# Arduino_MEGA_2560-Rev3_1.net
KiCad netlist of a schematic drawn in Altium Designer
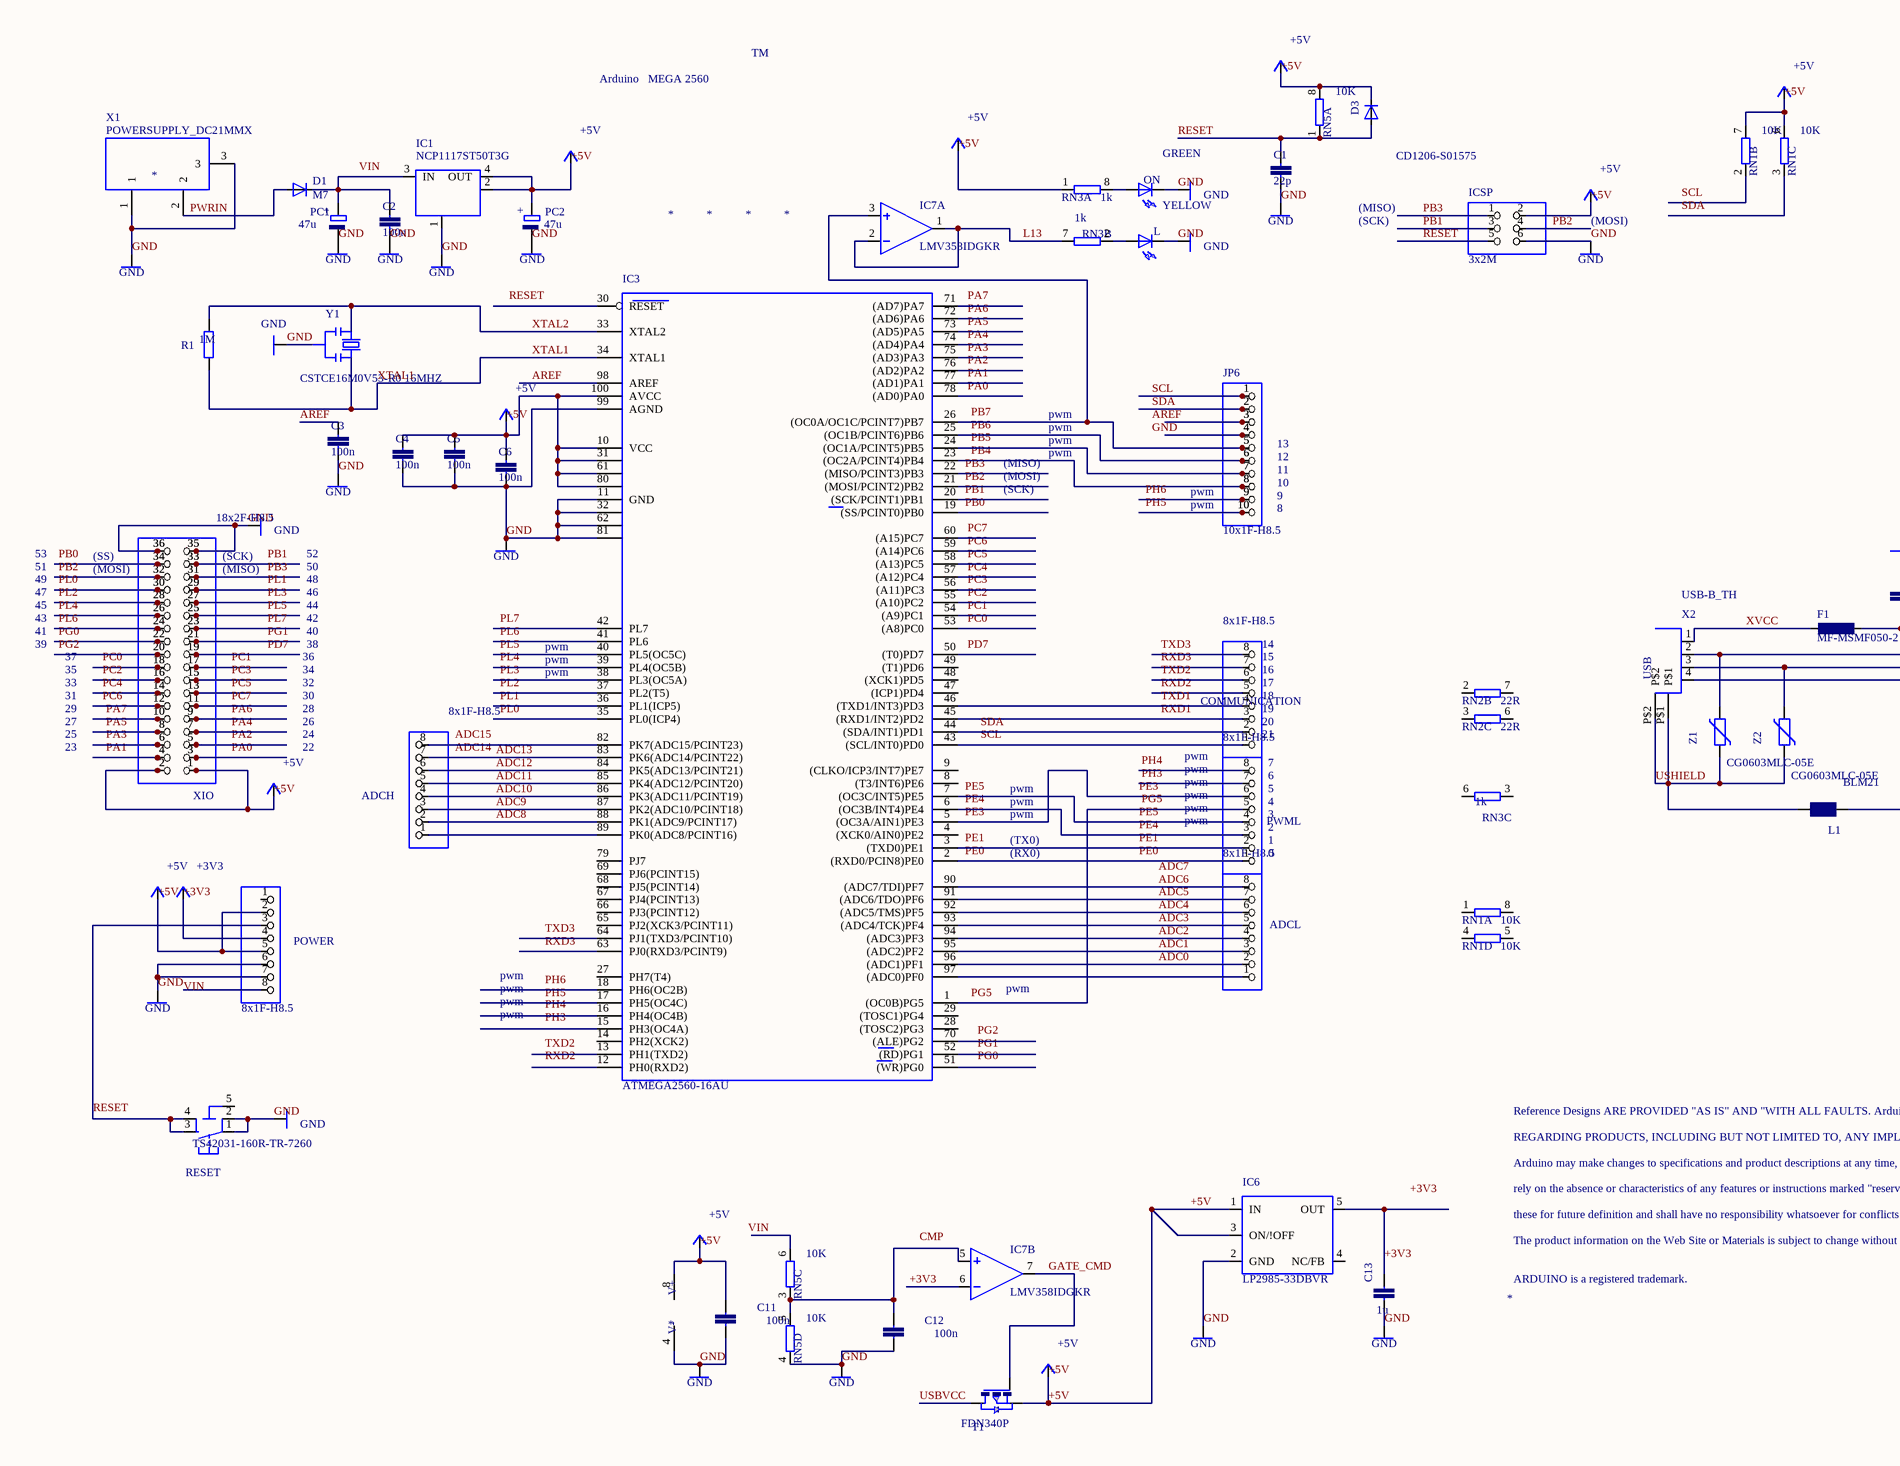
[diagram p0: Arduino_MEGA_2560-Rev3_1.SchDoc, left]
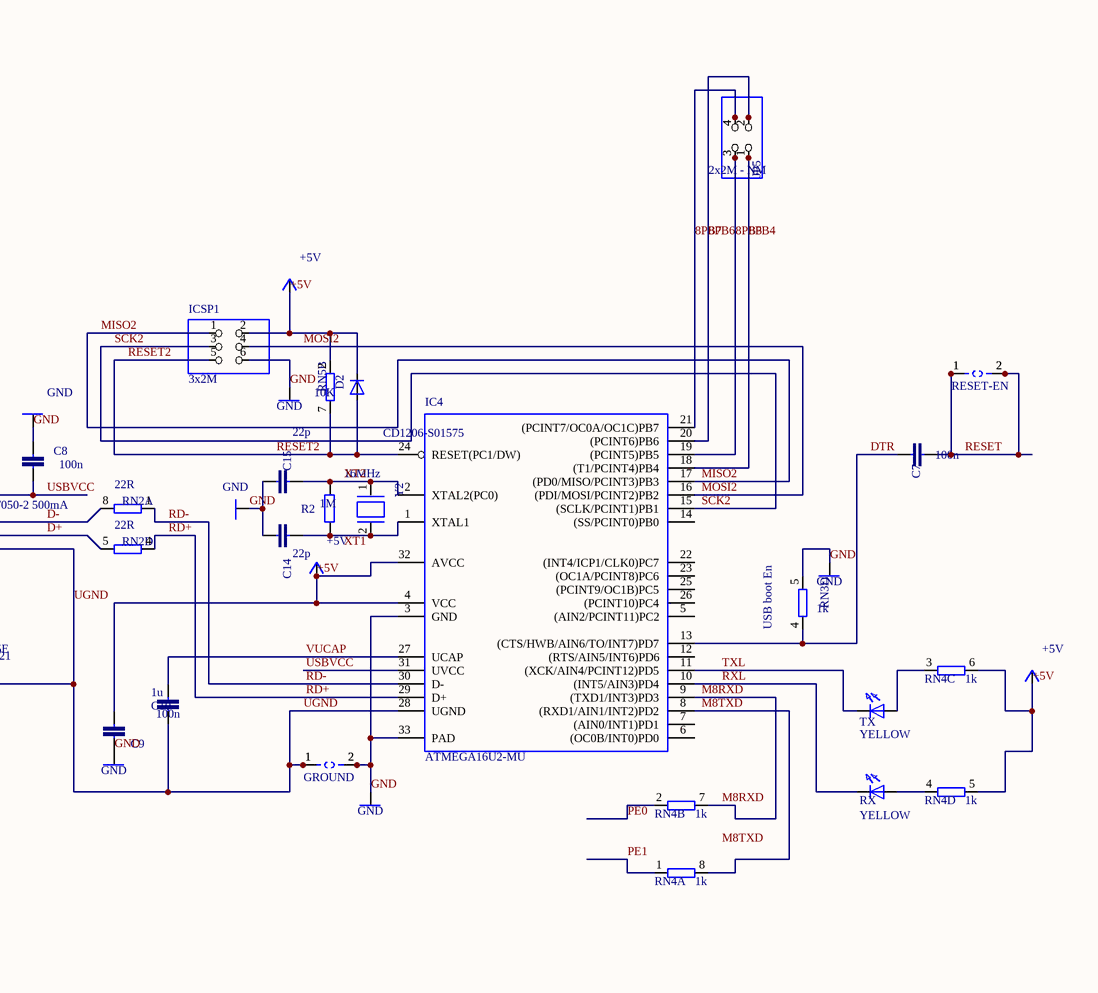
[diagram p1: Arduino_MEGA_2560-Rev3_1.SchDoc, right]

(export (version "E")
  (design (tool "Eeschema 10.0.6"))
  (components
    (comp (ref "+3V3") (value "+3V3") (libsource (lib "supply1") (part "+3V3")))
    (comp (ref "ADCH") (value "8x1F-H8.5") (footprint "1X08") (libsource (lib "SmartPrj") (part "PINHD-1X8")))
    (comp (ref "ADCL") (value "8x1F-H8.5") (footprint "1X08") (libsource (lib "SmartPrj") (part "PINHD-1X8")))
    (comp (ref "C1")
      (value "22p")
      (footprint "C0603-ROUND")
      (libsource (lib "SmartPrj") (part "C-EU0603-RND"))
    )
    (comp (ref "C2")
      (value "100n")
      (footprint "C0603-ROUND")
      (libsource (lib "SmartPrj") (part "C-EU0603-RND"))
    )
    (comp (ref "C3")
      (value "100n")
      (footprint "C0603-ROUND")
      (libsource (lib "SmartPrj") (part "C-EU0603-RND"))
    )
    (comp (ref "C4")
      (value "100n")
      (footprint "C0603-ROUND")
      (libsource (lib "SmartPrj") (part "C-EU0603-RND"))
    )
    (comp (ref "C5")
      (value "100n")
      (footprint "C0603-ROUND")
      (libsource (lib "SmartPrj") (part "C-EU0603-RND"))
    )
    (comp (ref "C6")
      (value "100n")
      (footprint "C0603-ROUND")
      (libsource (lib "SmartPrj") (part "C-EU0603-RND"))
    )
    (comp (ref "C7") (value "100n") (footprint "C0603-ROUND") (libsource (lib "") (part "C-EU0603-RND_4")))
    (comp (ref "C8") (value "100n") (footprint "C0603-ROUND") (libsource (lib "") (part "C-EU0603-RND_5")))
    (comp (ref "C9") (value "100n") (footprint "C0603-ROUND") (libsource (lib "") (part "C-EU0603-RND_3")))
    (comp (ref "C10")
      (value "1u")
      (footprint "C0603-ROUND")
      (libsource (lib "SmartPrj") (part "C-EU0603-RND"))
    )
    (comp (ref "C11") (value "100n") (footprint "C0603-ROUND") (libsource (lib "") (part "C-EU0603-RND_1")))
    (comp (ref "C12") (value "100n") (footprint "C0603-ROUND") (libsource (lib "") (part "C-EU0603-RND_1")))
    (comp (ref "C13") (value "1u") (footprint "C0603-ROUND") (libsource (lib "") (part "C-EU0603-RND_5")))
    (comp (ref "C14") (value "22p") (footprint "C0603-ROUND") (libsource (lib "") (part "C-EU0603-RND_2")))
    (comp (ref "C15") (value "22p") (footprint "C0603-ROUND") (libsource (lib "") (part "C-EU0603-RND_2")))
    (comp (ref "COMMUNICATION")
      (value "8x1F-H8.5")
      (footprint "1X08")
      (libsource (lib "SmartPrj") (part "PINHD-1X8"))
    )
    (comp (ref "D1") (value "M7") (footprint "SMB") (libsource (lib "diode") (part "DIODE-SMB")))
    (comp (ref "D2")
      (value "CD1206-S01575")
      (footprint "MINIMELF")
      (libsource (lib "diode") (part "DIODE-MINIMELF"))
    )
    (comp (ref "D3")
      (value "CD1206-S01575")
      (footprint "MINIMELF")
      (libsource (lib "diode") (part "DIODE-MINIMELF"))
    )
    (comp (ref "F1")
      (value "MF-MSMF050-2 500mA")
      (footprint "L1812")
      (libsource (lib "rcl") (part "L-EUL1812"))
    )
    (comp (ref "FD1")
      (value "*")
      (footprint "FIDUCIA-MOUNT")
      (libsource (lib "SmartPrj") (part "FIDUCIALMOUNT"))
    )
    (comp (ref "FD2")
      (value "*")
      (footprint "FIDUCIA-MOUNT")
      (libsource (lib "SmartPrj") (part "FIDUCIALMOUNT"))
    )
    (comp (ref "FD3")
      (value "*")
      (footprint "FIDUCIA-MOUNT")
      (libsource (lib "SmartPrj") (part "FIDUCIALMOUNT"))
    )
    (comp (ref "FD4")
      (value "*")
      (footprint "FIDUCIA-MOUNT")
      (libsource (lib "SmartPrj") (part "FIDUCIALMOUNT"))
    )
    (comp (ref "GND1") (value "GND") (libsource (lib "") (part "GND_1")))
    (comp (ref "GND2") (value "GND") (libsource (lib "") (part "GND_1")))
    (comp (ref "GND3") (value "GND") (libsource (lib "supply1") (part "GND")))
    (comp (ref "GND4") (value "GND") (libsource (lib "") (part "GND_1")))
    (comp (ref "GND5") (value "GND") (libsource (lib "") (part "GND_1")))
    (comp (ref "GND7") (value "GND") (libsource (lib "") (part "GND_1")))
    (comp (ref "GND8") (value "GND") (libsource (lib "") (part "GND_1")))
    (comp (ref "GND9") (value "GND") (libsource (lib "") (part "GND_1")))
    (comp (ref "GND10") (value "GND") (libsource (lib "") (part "GND_1")))
    (comp (ref "GND11") (value "GND") (libsource (lib "") (part "GND_1")))
    (comp (ref "GND12") (value "GND") (libsource (lib "supply1") (part "GND")))
    (comp (ref "GND13") (value "GND") (libsource (lib "") (part "GND_1")))
    (comp (ref "GND14") (value "GND") (libsource (lib "") (part "GND_1")))
    (comp (ref "GND15") (value "GND") (libsource (lib "") (part "GND_1")))
    (comp (ref "GND16") (value "GND") (libsource (lib "") (part "GND_1")))
    (comp (ref "GND18") (value "GND") (libsource (lib "") (part "GND_1")))
    (comp (ref "GND19") (value "GND") (libsource (lib "") (part "GND_1")))
    (comp (ref "GND20") (value "GND") (libsource (lib "supply1") (part "GND")))
    (comp (ref "GND22") (value "GND") (libsource (lib "") (part "GND_1")))
    (comp (ref "GND23") (value "GND") (libsource (lib "") (part "GND_1")))
    (comp (ref "GND24") (value "GND") (libsource (lib "") (part "GND_1")))
    (comp (ref "GND25") (value "GND") (libsource (lib "supply1") (part "GND")))
    (comp (ref "GND26") (value "GND") (libsource (lib "") (part "GND_1")))
    (comp (ref "GND28") (value "GND") (libsource (lib "") (part "GND_1")))
    (comp (ref "GND30") (value "GND") (libsource (lib "") (part "GND_1")))
    (comp (ref "GROUND") (value "~") (footprint "SJ") (libsource (lib "jumper") (part "SJ")))
    (comp (ref "IC1")
      (value "NCP1117ST50T3G")
      (footprint "SOT223")
      (libsource (lib "linear") (part "MC33269ST-3.3T3"))
    )
    (comp (ref "IC3")
      (value "ATMEGA2560-16AU")
      (footprint "TQFP100")
      (libsource (lib "SmartPrj") (part "ATMEGA25602560-16AU"))
    )
    (comp (ref "IC4")
      (value "ATMEGA16U2-MU")
      (footprint "MLF32")
      (libsource (lib "SmartPrj") (part "ATMEGA16U2-MU"))
    )
    (comp (ref "IC6")
      (value "LP2985-33DBVR")
      (footprint "SOT23-DBV")
      (libsource (lib "SmartPrj") (part "LP2985-XXDBVR33"))
    )
    (comp (ref "IC7")
      (value "LMV358IDGKR")
      (footprint "MSOP08")
      (libsource (lib "linear") (part "LMV358MMX"))
    )
    (comp (ref "ICSP") (value "3x2M") (footprint "2X03") (libsource (lib "SmartPrj") (part "PINHD-2X3")))
    (comp (ref "ICSP1") (value "3x2M") (footprint "2X03") (libsource (lib "SmartPrj") (part "PINHD-2X3")))
    (comp (ref "JP5") (value "2x2M - NM") (footprint "2X02") (libsource (lib "SmartPrj") (part "PINHD-2X2")))
    (comp (ref "JP6")
      (value "10x1F-H8.5")
      (footprint "1X10")
      (libsource (lib "SmartPrj") (part "PINHD-1X10_ARD"))
    )
    (comp (ref "L")
      (value "YELLOW")
      (footprint "CHIP-LED0805")
      (libsource (lib "led") (part "LEDCHIP-LED0805"))
    )
    (comp (ref "L1")
      (value "BLM21")
      (footprint "0805")
      (libsource (lib "wuerth-elektronik") (part "WE-CBF_0805"))
    )
    (comp (ref "ON")
      (value "GREEN")
      (footprint "CHIP-LED0805")
      (libsource (lib "led") (part "LEDCHIP-LED0805"))
    )
    (comp (ref "P+1") (value "+5V") (libsource (lib "supply1") (part "+5V")))
    (comp (ref "P+2") (value "+5V") (libsource (lib "") (part "+5V_1")))
    (comp (ref "P+3") (value "+5V") (libsource (lib "supply1") (part "+5V")))
    (comp (ref "P+4") (value "+5V") (libsource (lib "supply1") (part "+5V")))
    (comp (ref "P+5") (value "+5V") (libsource (lib "supply1") (part "+5V")))
    (comp (ref "P+7") (value "+5V") (libsource (lib "supply1") (part "+5V")))
    (comp (ref "P+8") (value "+5V") (libsource (lib "supply1") (part "+5V")))
    (comp (ref "P+9") (value "+5V") (libsource (lib "supply1") (part "+5V")))
    (comp (ref "P+10") (value "+5V") (libsource (lib "supply1") (part "+5V")))
    (comp (ref "P+11") (value "+5V") (libsource (lib "") (part "+5V_1")))
    (comp (ref "P+12") (value "+5V") (libsource (lib "supply1") (part "+5V")))
    (comp (ref "P+13") (value "+5V") (libsource (lib "supply1") (part "+5V")))
    (comp (ref "P+14") (value "+5V") (libsource (lib "supply1") (part "+5V")))
    (comp (ref "PC1") (value "47u") (footprint "PANASONIC_D") (libsource (lib "rcl") (part "CPOL-EUD")))
    (comp (ref "PC2") (value "47u") (footprint "PANASONIC_D") (libsource (lib "rcl") (part "CPOL-EUD")))
    (comp (ref "POWER")
      (value "8x1F-H8.5")
      (footprint "1X08")
      (libsource (lib "SmartPrj") (part "PINHD-1X8"))
    )
    (comp (ref "PWML") (value "8x1F-H8.5") (footprint "1X08") (libsource (lib "SmartPrj") (part "PINHD-1X8")))
    (comp (ref "R1") (value "1M") (footprint "R0603-ROUND") (libsource (lib "SmartPrj") (part "R-EU_R0603")))
    (comp (ref "R2") (value "1M") (footprint "R0603-ROUND") (libsource (lib "SmartPrj") (part "R-EU_R0603")))
    (comp (ref "RESET")
      (value "TS42031-160R-TR-7260")
      (footprint "TS42")
      (libsource (lib "SmartPrj") (part "TS42"))
    )
    (comp (ref "RESET-EN") (value "~") (footprint "SJ") (libsource (lib "jumper") (part "SJ")))
    (comp (ref "RN1") (value "10K") (footprint "CAT16") (libsource (lib "") (part "4R-NCAT16_7")))
    (comp (ref "RN2") (value "22R") (footprint "CAY16") (libsource (lib "") (part "4R-NCAY16_4")))
    (comp (ref "RN3") (value "1k") (footprint "CAY16") (libsource (lib "") (part "4R-NCAY16_6")))
    (comp (ref "RN4") (value "1k") (footprint "CAY16") (libsource (lib "") (part "4R-NCAY16_1")))
    (comp (ref "RN5") (value "10K") (footprint "CAT16") (libsource (lib "") (part "4R-NCAT16_3")))
    (comp (ref "RX")
      (value "YELLOW")
      (footprint "CHIP-LED0805")
      (libsource (lib "") (part "LEDCHIP-LED0805_1"))
    )
    (comp (ref "T1") (value "FDN340P") (footprint "SOT-23") (libsource (lib "zetex") (part "PMOSSOT23")))
    (comp (ref "TX")
      (value "YELLOW")
      (footprint "CHIP-LED0805")
      (libsource (lib "") (part "LEDCHIP-LED0805_1"))
    )
    (comp (ref "U$1") (value "*") (footprint "DISCLAIMER") (libsource (lib "SmartPrj") (part "DISCLAIMER")))
    (comp (ref "X1")
      (value "*")
      (footprint "POWERSUPPLY_DC-21MM")
      (libsource (lib "SmartPrj") (part "POWERSUPPLY_DC21MMX"))
    )
    (comp (ref "X2") (value "USB-B_TH") (footprint "PN61729") (libsource (lib "SmartPrj") (part "PN61729")))
    (comp (ref "XIO")
      (value "18x2F-H8.5")
      (footprint "2X18")
      (libsource (lib "SmartPrj") (part "PINHD-2X18"))
    )
    (comp (ref "Y1")
      (value "CSTCE16M0V53-R0 16MHZ")
      (footprint "RESONATOR")
      (libsource (lib "SmartPrj") (part "RESONATORMU"))
    )
    (comp (ref "Y2") (value "16MHz") (footprint "QS") (libsource (lib "SmartPrj") (part "XTAL/S")))
    (comp (ref "Z1")
      (value "CG0603MLC-05E")
      (footprint "CT/CN0603")
      (libsource (lib "varistor") (part "VARISTORCN0603"))
    )
    (comp (ref "Z2")
      (value "CG0603MLC-05E")
      (footprint "CT/CN0603")
      (libsource (lib "varistor") (part "VARISTORCN0603"))
    )
  )
  (nets
    (net (code "1") (name "/+3V3") (class "Default")
      (node (ref "+3V3") (pin "0") (pinfunction "+3V3_0") (pintype "passive"))
      (node (ref "C13") (pin "2") (pinfunction "2_2") (pintype "passive"))
      (node (ref "IC6") (pin "5") (pinfunction "OUT_5") (pintype "passive"))
      (node (ref "IC7") (pin "6") (pinfunction "-IN_6") (pintype "passive"))
      (node (ref "POWER") (pin "4") (pinfunction "4_4") (pintype "passive"))
    )
    (net (code "2") (name "/+5V") (class "Default")
      (node (ref "C11") (pin "2") (pinfunction "2_2") (pintype "passive"))
      (node (ref "C4") (pin "1") (pinfunction "1_1") (pintype "passive"))
      (node (ref "C5") (pin "1") (pinfunction "1_1") (pintype "passive"))
      (node (ref "C6") (pin "1") (pinfunction "1_1") (pintype "passive"))
      (node (ref "C9") (pin "1") (pinfunction "1_1") (pintype "passive"))
      (node (ref "D2") (pin "C") (pinfunction "C_C") (pintype "passive"))
      (node (ref "D3") (pin "C") (pinfunction "C_C") (pintype "passive"))
      (node (ref "IC1") (pin "2") (pinfunction "OUT@1_2") (pintype "passive"))
      (node (ref "IC1") (pin "4") (pinfunction "OUT_4") (pintype "passive"))
      (node (ref "IC3") (pin "10") (pinfunction "VCC_10") (pintype "passive"))
      (node (ref "IC3") (pin "100") (pinfunction "AVCC_100") (pintype "passive"))
      (node (ref "IC3") (pin "31") (pinfunction "VCC1_31") (pintype "passive"))
      (node (ref "IC3") (pin "61") (pinfunction "VCC2_61") (pintype "passive"))
      (node (ref "IC3") (pin "80") (pinfunction "VCC3_80") (pintype "passive"))
      (node (ref "IC4") (pin "32") (pinfunction "AVCC_32") (pintype "passive"))
      (node (ref "IC4") (pin "4") (pinfunction "VCC_4") (pintype "passive"))
      (node (ref "IC6") (pin "1") (pinfunction "IN_1") (pintype "passive"))
      (node (ref "IC6") (pin "3") (pinfunction "ON/!OFF_3") (pintype "passive"))
      (node (ref "IC7") (pin "8") (pinfunction "V+_8") (pintype "passive"))
      (node (ref "ICSP") (pin "2") (pinfunction "2_2") (pintype "passive"))
      (node (ref "ICSP1") (pin "2") (pinfunction "2_2") (pintype "passive"))
      (node (ref "P+1") (pin "0") (pinfunction "+5V_0") (pintype "passive"))
      (node (ref "P+10") (pin "0") (pinfunction "+5V_0") (pintype "passive"))
      (node (ref "P+11") (pin "0") (pinfunction "+5V_0") (pintype "passive"))
      (node (ref "P+12") (pin "0") (pinfunction "+5V_0") (pintype "passive"))
      (node (ref "P+13") (pin "0") (pinfunction "+5V_0") (pintype "passive"))
      (node (ref "P+14") (pin "0") (pinfunction "+5V_0") (pintype "passive"))
      (node (ref "P+2") (pin "0") (pinfunction "+5V_0") (pintype "passive"))
      (node (ref "P+3") (pin "0") (pinfunction "+5V_0") (pintype "passive"))
      (node (ref "P+4") (pin "0") (pinfunction "+5V_0") (pintype "passive"))
      (node (ref "P+5") (pin "0") (pinfunction "+5V_0") (pintype "passive"))
      (node (ref "P+7") (pin "0") (pinfunction "+5V_0") (pintype "passive"))
      (node (ref "P+8") (pin "0") (pinfunction "+5V_0") (pintype "passive"))
      (node (ref "P+9") (pin "0") (pinfunction "+5V_0") (pintype "passive"))
      (node (ref "PC2") (pin "+") (pinfunction "+_+") (pintype "passive"))
      (node (ref "POWER") (pin "2") (pinfunction "2_2") (pintype "passive"))
      (node (ref "POWER") (pin "5") (pinfunction "5_5") (pintype "passive"))
      (node (ref "RN1") (pin "6") (pinfunction "2_6") (pintype "passive"))
      (node (ref "RN1") (pin "7") (pinfunction "2_7") (pintype "passive"))
      (node (ref "RN3") (pin "1") (pinfunction "1_1") (pintype "passive"))
      (node (ref "RN4") (pin "5") (pinfunction "2_5") (pintype "passive"))
      (node (ref "RN4") (pin "6") (pinfunction "2_6") (pintype "passive"))
      (node (ref "RN5") (pin "2") (pinfunction "1_2") (pintype "passive"))
      (node (ref "RN5") (pin "8") (pinfunction "2_8") (pintype "passive"))
      (node (ref "T1") (pin "2") (pinfunction "S_2") (pintype "passive"))
      (node (ref "XIO") (pin "1") (pinfunction "1_1") (pintype "passive"))
      (node (ref "XIO") (pin "2") (pinfunction "2_2") (pintype "passive"))
    )
    (net (code "3") (name "/8PB4") (class "Default")
      (node (ref "IC4") (pin "18") (pinfunction "(T1/PCINT4)PB4_18") (pintype "passive"))
      (node (ref "JP5") (pin "1") (pinfunction "1_1") (pintype "passive"))
    )
    (net (code "4") (name "/8PB5") (class "Default")
      (node (ref "IC4") (pin "19") (pinfunction "(PCINT5)PB5_19") (pintype "passive"))
      (node (ref "JP5") (pin "3") (pinfunction "3_3") (pintype "passive"))
    )
    (net (code "5") (name "/8PB6") (class "Default")
      (node (ref "IC4") (pin "20") (pinfunction "(PCINT6)PB6_20") (pintype "passive"))
      (node (ref "JP5") (pin "2") (pinfunction "2_2") (pintype "passive"))
    )
    (net (code "6") (name "/8PB7") (class "Default")
      (node (ref "IC4") (pin "21") (pinfunction "(PCINT7/OC0A/OC1C)PB7_21") (pintype "passive"))
      (node (ref "JP5") (pin "4") (pinfunction "4_4") (pintype "passive"))
    )
    (net (code "7") (name "/ADC0") (class "Default")
      (node (ref "ADCL") (pin "2") (pinfunction "2_2") (pintype "passive"))
      (node (ref "IC3") (pin "96") (pinfunction "(ADC1)PF1_96") (pintype "passive"))
    )
    (net (code "8") (name "/ADC1") (class "Default")
      (node (ref "ADCL") (pin "3") (pinfunction "3_3") (pintype "passive"))
      (node (ref "IC3") (pin "95") (pinfunction "(ADC2)PF2_95") (pintype "passive"))
    )
    (net (code "9") (name "/ADC2") (class "Default")
      (node (ref "ADCL") (pin "4") (pinfunction "4_4") (pintype "passive"))
      (node (ref "IC3") (pin "94") (pinfunction "(ADC3)PF3_94") (pintype "passive"))
    )
    (net (code "10") (name "/ADC3") (class "Default")
      (node (ref "ADCL") (pin "5") (pinfunction "5_5") (pintype "passive"))
      (node (ref "IC3") (pin "93") (pinfunction "(ADC4/TCK)PF4_93") (pintype "passive"))
    )
    (net (code "11") (name "/ADC4") (class "Default")
      (node (ref "ADCL") (pin "6") (pinfunction "6_6") (pintype "passive"))
      (node (ref "IC3") (pin "92") (pinfunction "(ADC5/TMS)PF5_92") (pintype "passive"))
    )
    (net (code "12") (name "/ADC5") (class "Default")
      (node (ref "ADCL") (pin "7") (pinfunction "7_7") (pintype "passive"))
      (node (ref "IC3") (pin "91") (pinfunction "(ADC6/TDO)PF6_91") (pintype "passive"))
    )
    (net (code "13") (name "/ADC6") (class "Default")
      (node (ref "ADCL") (pin "8") (pinfunction "8_8") (pintype "passive"))
      (node (ref "IC3") (pin "90") (pinfunction "(ADC7/TDI)PF7_90") (pintype "passive"))
    )
    (net (code "15") (name "/ADC8") (class "Default")
      (node (ref "ADCH") (pin "2") (pinfunction "2_2") (pintype "passive"))
      (node (ref "IC3") (pin "88") (pinfunction "PK1(ADC9/PCINT17)_88") (pintype "passive"))
    )
    (net (code "16") (name "/ADC9") (class "Default")
      (node (ref "ADCH") (pin "3") (pinfunction "3_3") (pintype "passive"))
      (node (ref "IC3") (pin "87") (pinfunction "PK2(ADC10/PCINT18)_87") (pintype "passive"))
    )
    (net (code "17") (name "/ADC10") (class "Default")
      (node (ref "ADCH") (pin "4") (pinfunction "4_4") (pintype "passive"))
      (node (ref "IC3") (pin "86") (pinfunction "PK3(ADC11/PCINT19)_86") (pintype "passive"))
    )
    (net (code "18") (name "/ADC11") (class "Default")
      (node (ref "ADCH") (pin "5") (pinfunction "5_5") (pintype "passive"))
      (node (ref "IC3") (pin "85") (pinfunction "PK4(ADC12/PCINT20)_85") (pintype "passive"))
    )
    (net (code "19") (name "/ADC12") (class "Default")
      (node (ref "ADCH") (pin "6") (pinfunction "6_6") (pintype "passive"))
      (node (ref "IC3") (pin "84") (pinfunction "PK5(ADC13/PCINT21)_84") (pintype "passive"))
    )
    (net (code "20") (name "/ADC13") (class "Default")
      (node (ref "ADCH") (pin "7") (pinfunction "7_7") (pintype "passive"))
      (node (ref "IC3") (pin "83") (pinfunction "PK6(ADC14/PCINT22)_83") (pintype "passive"))
    )
    (net (code "23") (name "/AREF") (class "Default")
      (node (ref "C3") (pin "1") (pinfunction "1_1") (pintype "passive"))
      (node (ref "IC3") (pin "98") (pinfunction "AREF_98") (pintype "passive"))
    )
    (net (code "25") (name "/D+") (class "Default")
      (node (ref "RN2") (pin "5") (pinfunction "2_5") (pintype "passive"))
      (node (ref "X2") (pin "3") (pinfunction "3_3") (pintype "passive"))
      (node (ref "Z2") (pin "2") (pinfunction "2_2") (pintype "passive"))
    )
    (net (code "26") (name "/D-") (class "Default")
      (node (ref "RN2") (pin "8") (pinfunction "2_8") (pintype "passive"))
      (node (ref "X2") (pin "2") (pinfunction "2_2") (pintype "passive"))
      (node (ref "Z1") (pin "2") (pinfunction "2_2") (pintype "passive"))
    )
    (net (code "27") (name "/DTR") (class "Default")
      (node (ref "C7") (pin "1") (pinfunction "1_1") (pintype "passive"))
      (node (ref "IC4") (pin "13") (pinfunction "(CTS/HWB/AIN6/TO/INT7)PD7_13") (pintype "passive"))
      (node (ref "RN3") (pin "4") (pinfunction "1_4") (pintype "passive"))
    )
    (net (code "28") (name "/GATE_CMD") (class "Default")
      (node (ref "IC7") (pin "7") (pinfunction "OUT_7") (pintype "passive"))
      (node (ref "T1") (pin "3") (pinfunction "G_3") (pintype "passive"))
    )
    (net (code "29") (name "/GND") (class "Default")
      (node (ref "C1") (pin "2") (pinfunction "2_2") (pintype "passive"))
      (node (ref "C11") (pin "1") (pinfunction "1_1") (pintype "passive"))
      (node (ref "C12") (pin "1") (pinfunction "1_1") (pintype "passive"))
      (node (ref "C13") (pin "1") (pinfunction "1_1") (pintype "passive"))
      (node (ref "C14") (pin "2") (pinfunction "2_2") (pintype "passive"))
      (node (ref "C15") (pin "2") (pinfunction "2_2") (pintype "passive"))
      (node (ref "C2") (pin "2") (pinfunction "2_2") (pintype "passive"))
      (node (ref "C3") (pin "2") (pinfunction "2_2") (pintype "passive"))
      (node (ref "C4") (pin "2") (pinfunction "2_2") (pintype "passive"))
      (node (ref "C5") (pin "2") (pinfunction "2_2") (pintype "passive"))
      (node (ref "C6") (pin "2") (pinfunction "2_2") (pintype "passive"))
      (node (ref "C8") (pin "2") (pinfunction "2_2") (pintype "passive"))
      (node (ref "C9") (pin "2") (pinfunction "2_2") (pintype "passive"))
      (node (ref "GND1") (pin "0") (pinfunction "GND_0") (pintype "passive"))
      (node (ref "GND10") (pin "0") (pinfunction "GND_0") (pintype "passive"))
      (node (ref "GND11") (pin "0") (pinfunction "GND_0") (pintype "passive"))
      (node (ref "GND12") (pin "0") (pinfunction "GND_0") (pintype "passive"))
      (node (ref "GND13") (pin "0") (pinfunction "GND_0") (pintype "passive"))
      (node (ref "GND14") (pin "0") (pinfunction "GND_0") (pintype "passive"))
      (node (ref "GND15") (pin "0") (pinfunction "GND_0") (pintype "passive"))
      (node (ref "GND16") (pin "0") (pinfunction "GND_0") (pintype "passive"))
      (node (ref "GND18") (pin "0") (pinfunction "GND_0") (pintype "passive"))
      (node (ref "GND19") (pin "0") (pinfunction "GND_0") (pintype "passive"))
      (node (ref "GND2") (pin "0") (pinfunction "GND_0") (pintype "passive"))
      (node (ref "GND20") (pin "0") (pinfunction "GND_0") (pintype "passive"))
      (node (ref "GND22") (pin "0") (pinfunction "GND_0") (pintype "passive"))
      (node (ref "GND23") (pin "0") (pinfunction "GND_0") (pintype "passive"))
      (node (ref "GND24") (pin "0") (pinfunction "GND_0") (pintype "passive"))
      (node (ref "GND25") (pin "0") (pinfunction "GND_0") (pintype "passive"))
      (node (ref "GND26") (pin "0") (pinfunction "GND_0") (pintype "passive"))
      (node (ref "GND28") (pin "0") (pinfunction "GND_0") (pintype "passive"))
      (node (ref "GND3") (pin "0") (pinfunction "GND_0") (pintype "passive"))
      (node (ref "GND30") (pin "0") (pinfunction "GND_0") (pintype "passive"))
      (node (ref "GND4") (pin "0") (pinfunction "GND_0") (pintype "passive"))
      (node (ref "GND5") (pin "0") (pinfunction "GND_0") (pintype "passive"))
      (node (ref "GND7") (pin "0") (pinfunction "GND_0") (pintype "passive"))
      (node (ref "GND8") (pin "0") (pinfunction "GND_0") (pintype "passive"))
      (node (ref "GND9") (pin "0") (pinfunction "GND_0") (pintype "passive"))
      (node (ref "GROUND") (pin "2") (pinfunction "2_2") (pintype "passive"))
      (node (ref "IC1") (pin "1") (pinfunction "GND/ADJ_1") (pintype "passive"))
      (node (ref "IC3") (pin "11") (pinfunction "GND_11") (pintype "passive"))
      (node (ref "IC3") (pin "32") (pinfunction "GND1_32") (pintype "passive"))
      (node (ref "IC3") (pin "62") (pinfunction "GND2_62") (pintype "passive"))
      (node (ref "IC3") (pin "81") (pinfunction "GND3_81") (pintype "passive"))
      (node (ref "IC3") (pin "99") (pinfunction "AGND_99") (pintype "passive"))
      (node (ref "IC4") (pin "3") (pinfunction "GND_3") (pintype "passive"))
      (node (ref "IC4") (pin "33") (pinfunction "PAD_33") (pintype "passive"))
      (node (ref "IC6") (pin "2") (pinfunction "GND_2") (pintype "passive"))
      (node (ref "IC7") (pin "4") (pinfunction "V-_4") (pintype "passive"))
      (node (ref "ICSP") (pin "6") (pinfunction "6_6") (pintype "passive"))
      (node (ref "ICSP1") (pin "6") (pinfunction "6_6") (pintype "passive"))
      (node (ref "L") (pin "C") (pinfunction "C_C") (pintype "passive"))
      (node (ref "ON") (pin "C") (pinfunction "C_C") (pintype "passive"))
      (node (ref "PC1") (pin "-") (pinfunction "-_-") (pintype "passive"))
      (node (ref "PC2") (pin "-") (pinfunction "-_-") (pintype "passive"))
      (node (ref "POWER") (pin "6") (pinfunction "6_6") (pintype "passive"))
      (node (ref "POWER") (pin "7") (pinfunction "7_7") (pintype "passive"))
      (node (ref "RESET") (pin "1") (pinfunction "1_1") (pintype "passive"))
      (node (ref "RESET") (pin "2") (pinfunction "2_2") (pintype "passive"))
      (node (ref "RN3") (pin "5") (pinfunction "2_5") (pintype "passive"))
      (node (ref "RN5") (pin "4") (pinfunction "1_4") (pintype "passive"))
      (node (ref "X1") (pin "1") (pinfunction "1_1") (pintype "passive"))
      (node (ref "X1") (pin "3") (pinfunction "3_3") (pintype "passive"))
      (node (ref "XIO") (pin "35") (pinfunction "35_35") (pintype "passive"))
      (node (ref "XIO") (pin "36") (pinfunction "36_36") (pintype "passive"))
      (node (ref "Y1") (pin "2") (pinfunction "2_2") (pintype "passive"))
    )
    (net (code "30") (name "/L13") (class "Default")
      (node (ref "IC7") (pin "1") (pinfunction "OUT_1") (pintype "passive"))
      (node (ref "IC7") (pin "2") (pinfunction "-IN_2") (pintype "passive"))
      (node (ref "RN3") (pin "7") (pinfunction "2_7") (pintype "passive"))
    )
    (net (code "31") (name "/M8RXD") (class "Default")
      (node (ref "IC4") (pin "9") (pinfunction "(TXD1/INT3)PD3_9") (pintype "passive"))
      (node (ref "RN4") (pin "7") (pinfunction "2_7") (pintype "passive"))
    )
    (net (code "32") (name "/M8TXD") (class "Default")
      (node (ref "IC4") (pin "8") (pinfunction "(RXD1/AIN1/INT2)PD2_8") (pintype "passive"))
      (node (ref "RN4") (pin "8") (pinfunction "2_8") (pintype "passive"))
    )
    (net (code "33") (name "/MISO2") (class "Default")
      (node (ref "IC4") (pin "17") (pinfunction "(PD0/MISO/PCINT3)PB3_17") (pintype "passive"))
      (node (ref "ICSP1") (pin "1") (pinfunction "1_1") (pintype "passive"))
    )
    (net (code "34") (name "/MOSI2") (class "Default")
      (node (ref "IC4") (pin "16") (pinfunction "(PDI/MOSI/PCINT2)PB2_16") (pintype "passive"))
      (node (ref "ICSP1") (pin "4") (pinfunction "4_4") (pintype "passive"))
    )
    (net (code "44") (name "/PB1") (class "Default")
      (node (ref "ICSP") (pin "3") (pinfunction "3_3") (pintype "passive"))
    )
    (net (code "45") (name "/PB2") (class "Default")
      (node (ref "ICSP") (pin "4") (pinfunction "4_4") (pintype "passive"))
    )
    (net (code "46") (name "/PB3") (class "Default")
      (node (ref "ICSP") (pin "1") (pinfunction "1_1") (pintype "passive"))
    )
    (net (code "60") (name "/PE0") (class "Default")
      (node (ref "RN4") (pin "2") (pinfunction "1_2") (pintype "passive"))
    )
    (net (code "61") (name "/PE1") (class "Default")
      (node (ref "RN4") (pin "1") (pinfunction "1_1") (pintype "passive"))
    )
    (net (code "81") (name "/PWRIN") (class "Default")
      (node (ref "D1") (pin "A") (pinfunction "A_A") (pintype "passive"))
      (node (ref "X1") (pin "2") (pinfunction "2_2") (pintype "passive"))
    )
    (net (code "82") (name "/RD+") (class "Default")
      (node (ref "IC4") (pin "29") (pinfunction "D+_29") (pintype "passive"))
      (node (ref "RN2") (pin "4") (pinfunction "1_4") (pintype "passive"))
    )
    (net (code "83") (name "/RD-") (class "Default")
      (node (ref "IC4") (pin "30") (pinfunction "D-_30") (pintype "passive"))
      (node (ref "RN2") (pin "1") (pinfunction "1_1") (pintype "passive"))
    )
    (net (code "84") (name "/RESET") (class "Default")
      (node (ref "C1") (pin "1") (pinfunction "1_1") (pintype "passive"))
      (node (ref "C7") (pin "2") (pinfunction "2_2") (pintype "passive"))
      (node (ref "D3") (pin "A") (pinfunction "A_A") (pintype "passive"))
      (node (ref "ICSP") (pin "5") (pinfunction "5_5") (pintype "passive"))
      (node (ref "POWER") (pin "3") (pinfunction "3_3") (pintype "passive"))
      (node (ref "RESET") (pin "3") (pinfunction "3_3") (pintype "passive"))
      (node (ref "RESET") (pin "4") (pinfunction "4_4") (pintype "passive"))
      (node (ref "RESET-EN") (pin "1") (pinfunction "1_1") (pintype "passive"))
      (node (ref "RESET-EN") (pin "2") (pinfunction "2_2") (pintype "passive"))
      (node (ref "RN5") (pin "1") (pinfunction "1_1") (pintype "passive"))
    )
    (net (code "85") (name "/RESET2") (class "Default")
      (node (ref "D2") (pin "A") (pinfunction "A_A") (pintype "passive"))
      (node (ref "IC4") (pin "24") (pinfunction "RESET(PC1/DW)_24") (pintype "passive"))
      (node (ref "ICSP1") (pin "5") (pinfunction "5_5") (pintype "passive"))
      (node (ref "RN5") (pin "7") (pinfunction "2_7") (pintype "passive"))
    )
    (net (code "89") (name "/RXL") (class "Default")
      (node (ref "IC4") (pin "10") (pinfunction "(INT5/AIN3)PD4_10") (pintype "passive"))
      (node (ref "RX") (pin "C") (pinfunction "C_C") (pintype "passive"))
    )
    (net (code "90") (name "/SCK2") (class "Default")
      (node (ref "IC4") (pin "15") (pinfunction "(SCLK/PCINT1)PB1_15") (pintype "passive"))
      (node (ref "ICSP1") (pin "3") (pinfunction "3_3") (pintype "passive"))
    )
    (net (code "91") (name "/SCL") (class "Default")
      (node (ref "JP6") (pin "1") (pinfunction "1_1") (pintype "passive"))
    )
    (net (code "92") (name "/SDA") (class "Default")
      (node (ref "JP6") (pin "2") (pinfunction "2_2") (pintype "passive"))
    )
    (net (code "96") (name "/TXL") (class "Default")
      (node (ref "IC4") (pin "11") (pinfunction "(XCK/AIN4/PCINT12)PD5_11") (pintype "passive"))
      (node (ref "TX") (pin "C") (pinfunction "C_C") (pintype "passive"))
    )
    (net (code "97") (name "/UGND") (class "Default")
      (node (ref "C10") (pin "2") (pinfunction "2_2") (pintype "passive"))
      (node (ref "GROUND") (pin "1") (pinfunction "1_1") (pintype "passive"))
      (node (ref "IC4") (pin "28") (pinfunction "UGND_28") (pintype "passive"))
      (node (ref "L1") (pin "1") (pinfunction "1_1") (pintype "passive"))
      (node (ref "X2") (pin "4") (pinfunction "4_4") (pintype "passive"))
    )
    (net (code "98") (name "/USBVCC") (class "Default")
      (node (ref "C8") (pin "1") (pinfunction "1_1") (pintype "passive"))
      (node (ref "F1") (pin "1") (pinfunction "1_1") (pintype "passive"))
      (node (ref "IC4") (pin "31") (pinfunction "UVCC_31") (pintype "passive"))
      (node (ref "T1") (pin "1") (pinfunction "D_1") (pintype "passive"))
    )
    (net (code "99") (name "/USHIELD") (class "Default")
      (node (ref "L1") (pin "2") (pinfunction "2_2") (pintype "passive"))
      (node (ref "X2") (pin "P$1") (pinfunction "P$1_P$1") (pintype "passive"))
      (node (ref "X2") (pin "P$2") (pinfunction "P$2_P$2") (pintype "passive"))
      (node (ref "Z1") (pin "1") (pinfunction "1_1") (pintype "passive"))
      (node (ref "Z2") (pin "1") (pinfunction "1_1") (pintype "passive"))
    )
    (net (code "101") (name "/VUCAP") (class "Default")
      (node (ref "C10") (pin "1") (pinfunction "1_1") (pintype "passive"))
      (node (ref "IC4") (pin "27") (pinfunction "UCAP_27") (pintype "passive"))
    )
    (net (code "103") (name "/XT2") (class "Default")
      (node (ref "C15") (pin "1") (pinfunction "1_1") (pintype "passive"))
      (node (ref "IC4") (pin "2") (pinfunction "XTAL2(PC0)_2") (pintype "passive"))
      (node (ref "R2") (pin "2") (pinfunction "2_2") (pintype "passive"))
      (node (ref "Y2") (pin "1") (pinfunction "1_1") (pintype "passive"))
    )
    (net (code "104") (name "/XTAL1") (class "Default")
      (node (ref "IC3") (pin "34") (pinfunction "XTAL1_34") (pintype "passive"))
      (node (ref "R1") (pin "1") (pinfunction "1_1") (pintype "passive"))
      (node (ref "Y1") (pin "3") (pinfunction "3_3") (pintype "passive"))
    )
    (net (code "105") (name "/XTAL2") (class "Default")
      (node (ref "IC3") (pin "33") (pinfunction "XTAL2_33") (pintype "passive"))
      (node (ref "R1") (pin "2") (pinfunction "2_2") (pintype "passive"))
      (node (ref "Y1") (pin "1") (pinfunction "1_1") (pintype "passive"))
    )
    (net (code "106") (name "/XVCC") (class "Default")
      (node (ref "F1") (pin "2") (pinfunction "2_2") (pintype "passive"))
      (node (ref "X2") (pin "1") (pinfunction "1_1") (pintype "passive"))
    )
    (net (code "107") (name "Net-(IC1-IN)") (class "Default")
      (node (ref "C2") (pin "1") (pinfunction "1_1") (pintype "passive"))
      (node (ref "D1") (pin "C") (pinfunction "C_C") (pintype "passive"))
      (node (ref "IC1") (pin "3") (pinfunction "IN_3") (pintype "passive"))
      (node (ref "PC1") (pin "+") (pinfunction "+_+") (pintype "passive"))
    )
    (net (code "108") (name "Net-(IC3-(ADC0)PF0)") (class "Default")
      (node (ref "ADCL") (pin "1") (pinfunction "1_1") (pintype "passive"))
      (node (ref "IC3") (pin "97") (pinfunction "(ADC0)PF0_97") (pintype "passive"))
    )
    (net (code "109") (name "Net-(IC3-(OC0A{slash}OC1C{slash}PCINT7)PB7)") (class "Default")
      (node (ref "IC3") (pin "26") (pinfunction "(OC0A/OC1C/PCINT7)PB7_26") (pintype "passive"))
      (node (ref "IC7") (pin "3") (pinfunction "+IN_3") (pintype "passive"))
      (node (ref "JP6") (pin "5") (pinfunction "5_5") (pintype "passive"))
    )
    (net (code "110") (name "Net-(IC3-(OC0B)PG5)") (class "Default")
      (node (ref "IC3") (pin "1") (pinfunction "(OC0B)PG5_1") (pintype "passive"))
      (node (ref "PWML") (pin "5") (pinfunction "5_5") (pintype "passive"))
    )
    (net (code "111") (name "Net-(IC3-(OC1A{slash}PCINT5)PB5)") (class "Default")
      (node (ref "IC3") (pin "24") (pinfunction "(OC1A/PCINT5)PB5_24") (pintype "passive"))
      (node (ref "JP6") (pin "7") (pinfunction "7_7") (pintype "passive"))
    )
    (net (code "112") (name "Net-(IC3-(OC1B{slash}PCINT6)PB6)") (class "Default")
      (node (ref "IC3") (pin "25") (pinfunction "(OC1B/PCINT6)PB6_25") (pintype "passive"))
      (node (ref "JP6") (pin "6") (pinfunction "6_6") (pintype "passive"))
    )
    (net (code "113") (name "Net-(IC3-(OC2A{slash}PCINT4)PB4)") (class "Default")
      (node (ref "IC3") (pin "23") (pinfunction "(OC2A/PCINT4)PB4_23") (pintype "passive"))
      (node (ref "JP6") (pin "8") (pinfunction "8_8") (pintype "passive"))
    )
    (net (code "114") (name "Net-(IC3-(OC3A{slash}AIN1)PE3)") (class "Default")
      (node (ref "IC3") (pin "5") (pinfunction "(OC3A/AIN1)PE3_5") (pintype "passive"))
      (node (ref "PWML") (pin "6") (pinfunction "6_6") (pintype "passive"))
    )
    (net (code "115") (name "Net-(IC3-(OC3B{slash}INT4)PE4)") (class "Default")
      (node (ref "IC3") (pin "6") (pinfunction "(OC3B/INT4)PE4_6") (pintype "passive"))
      (node (ref "PWML") (pin "3") (pinfunction "3_3") (pintype "passive"))
    )
    (net (code "116") (name "Net-(IC3-(OC3C{slash}INT5)PE5)") (class "Default")
      (node (ref "IC3") (pin "7") (pinfunction "(OC3C/INT5)PE5_7") (pintype "passive"))
      (node (ref "PWML") (pin "4") (pinfunction "4_4") (pintype "passive"))
    )
    (net (code "117") (name "Net-(IC3-(RXD0{slash}PCIN8)PE0)") (class "Default")
      (node (ref "IC3") (pin "2") (pinfunction "(RXD0/PCIN8)PE0_2") (pintype "passive"))
      (node (ref "PWML") (pin "1") (pinfunction "1_1") (pintype "passive"))
    )
    (net (code "118") (name "Net-(IC3-(RXD1{slash}INT2)PD2)") (class "Default")
      (node (ref "COMMUNICATION") (pin "3") (pinfunction "3_3") (pintype "passive"))
      (node (ref "IC3") (pin "45") (pinfunction "(RXD1/INT2)PD2_45") (pintype "passive"))
    )
    (net (code "119") (name "Net-(IC3-(SCL{slash}INT0)PD0)") (class "Default")
      (node (ref "COMMUNICATION") (pin "1") (pinfunction "1_1") (pintype "passive"))
      (node (ref "IC3") (pin "43") (pinfunction "(SCL/INT0)PD0_43") (pintype "passive"))
    )
    (net (code "120") (name "Net-(IC3-(SDA{slash}INT1)PD1)") (class "Default")
      (node (ref "COMMUNICATION") (pin "2") (pinfunction "2_2") (pintype "passive"))
      (node (ref "IC3") (pin "44") (pinfunction "(SDA/INT1)PD1_44") (pintype "passive"))
    )
    (net (code "121") (name "Net-(IC3-(TXD0)PE1)") (class "Default")
      (node (ref "IC3") (pin "3") (pinfunction "(TXD0)PE1_3") (pintype "passive"))
      (node (ref "PWML") (pin "2") (pinfunction "2_2") (pintype "passive"))
    )
    (net (code "122") (name "Net-(IC3-(TXD1{slash}INT3)PD3)") (class "Default")
      (node (ref "COMMUNICATION") (pin "4") (pinfunction "4_4") (pintype "passive"))
      (node (ref "IC3") (pin "46") (pinfunction "(TXD1/INT3)PD3_46") (pintype "passive"))
    )
    (net (code "123") (name "Net-(IC3-PK0(ADC8{slash}PCINT16))") (class "Default")
      (node (ref "ADCH") (pin "1") (pinfunction "1_1") (pintype "passive"))
      (node (ref "IC3") (pin "89") (pinfunction "PK0(ADC8/PCINT16)_89") (pintype "passive"))
    )
    (net (code "124") (name "Net-(IC3-PK7(ADC15{slash}PCINT23))") (class "Default")
      (node (ref "ADCH") (pin "8") (pinfunction "8_8") (pintype "passive"))
      (node (ref "IC3") (pin "82") (pinfunction "PK7(ADC15/PCINT23)_82") (pintype "passive"))
    )
    (net (code "125") (name "Net-(IC4-XTAL1)") (class "Default")
      (node (ref "C14") (pin "1") (pinfunction "1_1") (pintype "passive"))
      (node (ref "IC4") (pin "1") (pinfunction "XTAL1_1") (pintype "passive"))
      (node (ref "R2") (pin "1") (pinfunction "1_1") (pintype "passive"))
      (node (ref "Y2") (pin "2") (pinfunction "2_2") (pintype "passive"))
    )
    (net (code "126") (name "Net-(IC7B-+IN)") (class "Default")
      (node (ref "C12") (pin "2") (pinfunction "2_2") (pintype "passive"))
      (node (ref "IC7") (pin "5") (pinfunction "+IN_5") (pintype "passive"))
      (node (ref "RN5") (pin "3") (pinfunction "1_3") (pintype "passive"))
      (node (ref "RN5") (pin "5") (pinfunction "2_5") (pintype "passive"))
    )
    (net (code "127") (name "Net-(JP6-Pad3)") (class "Default")
      (node (ref "JP6") (pin "3") (pinfunction "3_3") (pintype "passive"))
    )
    (net (code "128") (name "Net-(JP6-Pad4)") (class "Default")
      (node (ref "JP6") (pin "4") (pinfunction "4_4") (pintype "passive"))
    )
    (net (code "129") (name "Net-(JP6-Pad9)") (class "Default")
      (node (ref "JP6") (pin "9") (pinfunction "9_9") (pintype "passive"))
    )
    (net (code "130") (name "Net-(JP6-Pad10)") (class "Default")
      (node (ref "JP6") (pin "10") (pinfunction "10_10") (pintype "passive"))
    )
    (net (code "131") (name "Net-(RN3A-2)") (class "Default")
      (node (ref "ON") (pin "A") (pinfunction "A_A") (pintype "passive"))
      (node (ref "RN3") (pin "8") (pinfunction "2_8") (pintype "passive"))
    )
    (net (code "132") (name "Net-(RN3B-1)") (class "Default")
      (node (ref "L") (pin "A") (pinfunction "A_A") (pintype "passive"))
      (node (ref "RN3") (pin "2") (pinfunction "1_2") (pintype "passive"))
    )
    (net (code "133") (name "Net-(RN4C-1)") (class "Default")
      (node (ref "RN4") (pin "3") (pinfunction "1_3") (pintype "passive"))
      (node (ref "TX") (pin "A") (pinfunction "A_A") (pintype "passive"))
    )
    (net (code "134") (name "Net-(RN4D-1)") (class "Default")
      (node (ref "RN4") (pin "4") (pinfunction "1_4") (pintype "passive"))
      (node (ref "RX") (pin "A") (pinfunction "A_A") (pintype "passive"))
    )
    (net (code "135") (name "Net-(XIO-Pad3)") (class "Default")
      (node (ref "XIO") (pin "3") (pinfunction "3_3") (pintype "passive"))
    )
    (net (code "136") (name "Net-(XIO-Pad4)") (class "Default")
      (node (ref "XIO") (pin "4") (pinfunction "4_4") (pintype "passive"))
    )
    (net (code "137") (name "Net-(XIO-Pad5)") (class "Default")
      (node (ref "XIO") (pin "5") (pinfunction "5_5") (pintype "passive"))
    )
    (net (code "138") (name "Net-(XIO-Pad6)") (class "Default")
      (node (ref "XIO") (pin "6") (pinfunction "6_6") (pintype "passive"))
    )
    (net (code "139") (name "Net-(XIO-Pad7)") (class "Default")
      (node (ref "XIO") (pin "7") (pinfunction "7_7") (pintype "passive"))
    )
    (net (code "140") (name "Net-(XIO-Pad8)") (class "Default")
      (node (ref "XIO") (pin "8") (pinfunction "8_8") (pintype "passive"))
    )
    (net (code "141") (name "Net-(XIO-Pad9)") (class "Default")
      (node (ref "XIO") (pin "9") (pinfunction "9_9") (pintype "passive"))
    )
    (net (code "142") (name "Net-(XIO-Pad10)") (class "Default")
      (node (ref "XIO") (pin "10") (pinfunction "10_10") (pintype "passive"))
    )
    (net (code "143") (name "Net-(XIO-Pad11)") (class "Default")
      (node (ref "XIO") (pin "11") (pinfunction "11_11") (pintype "passive"))
    )
    (net (code "144") (name "Net-(XIO-Pad12)") (class "Default")
      (node (ref "XIO") (pin "12") (pinfunction "12_12") (pintype "passive"))
    )
    (net (code "145") (name "Net-(XIO-Pad13)") (class "Default")
      (node (ref "XIO") (pin "13") (pinfunction "13_13") (pintype "passive"))
    )
    (net (code "146") (name "Net-(XIO-Pad14)") (class "Default")
      (node (ref "XIO") (pin "14") (pinfunction "14_14") (pintype "passive"))
    )
    (net (code "147") (name "Net-(XIO-Pad15)") (class "Default")
      (node (ref "XIO") (pin "15") (pinfunction "15_15") (pintype "passive"))
    )
    (net (code "148") (name "Net-(XIO-Pad16)") (class "Default")
      (node (ref "XIO") (pin "16") (pinfunction "16_16") (pintype "passive"))
    )
    (net (code "149") (name "Net-(XIO-Pad17)") (class "Default")
      (node (ref "XIO") (pin "17") (pinfunction "17_17") (pintype "passive"))
    )
    (net (code "150") (name "Net-(XIO-Pad18)") (class "Default")
      (node (ref "XIO") (pin "18") (pinfunction "18_18") (pintype "passive"))
    )
    (net (code "151") (name "Net-(XIO-Pad19)") (class "Default")
      (node (ref "XIO") (pin "19") (pinfunction "19_19") (pintype "passive"))
    )
    (net (code "152") (name "Net-(XIO-Pad20)") (class "Default")
      (node (ref "XIO") (pin "20") (pinfunction "20_20") (pintype "passive"))
    )
    (net (code "153") (name "Net-(XIO-Pad21)") (class "Default")
      (node (ref "XIO") (pin "21") (pinfunction "21_21") (pintype "passive"))
    )
    (net (code "154") (name "Net-(XIO-Pad22)") (class "Default")
      (node (ref "XIO") (pin "22") (pinfunction "22_22") (pintype "passive"))
    )
    (net (code "155") (name "Net-(XIO-Pad23)") (class "Default")
      (node (ref "XIO") (pin "23") (pinfunction "23_23") (pintype "passive"))
    )
    (net (code "156") (name "Net-(XIO-Pad24)") (class "Default")
      (node (ref "XIO") (pin "24") (pinfunction "24_24") (pintype "passive"))
    )
    (net (code "157") (name "Net-(XIO-Pad25)") (class "Default")
      (node (ref "XIO") (pin "25") (pinfunction "25_25") (pintype "passive"))
    )
    (net (code "158") (name "Net-(XIO-Pad26)") (class "Default")
      (node (ref "XIO") (pin "26") (pinfunction "26_26") (pintype "passive"))
    )
    (net (code "159") (name "Net-(XIO-Pad27)") (class "Default")
      (node (ref "XIO") (pin "27") (pinfunction "27_27") (pintype "passive"))
    )
    (net (code "160") (name "Net-(XIO-Pad28)") (class "Default")
      (node (ref "XIO") (pin "28") (pinfunction "28_28") (pintype "passive"))
    )
    (net (code "161") (name "Net-(XIO-Pad29)") (class "Default")
      (node (ref "XIO") (pin "29") (pinfunction "29_29") (pintype "passive"))
    )
    (net (code "162") (name "Net-(XIO-Pad30)") (class "Default")
      (node (ref "XIO") (pin "30") (pinfunction "30_30") (pintype "passive"))
    )
    (net (code "163") (name "Net-(XIO-Pad31)") (class "Default")
      (node (ref "XIO") (pin "31") (pinfunction "31_31") (pintype "passive"))
    )
    (net (code "164") (name "Net-(XIO-Pad32)") (class "Default")
      (node (ref "XIO") (pin "32") (pinfunction "32_32") (pintype "passive"))
    )
    (net (code "165") (name "Net-(XIO-Pad33)") (class "Default")
      (node (ref "XIO") (pin "33") (pinfunction "33_33") (pintype "passive"))
    )
    (net (code "166") (name "Net-(XIO-Pad34)") (class "Default")
      (node (ref "XIO") (pin "34") (pinfunction "34_34") (pintype "passive"))
    )
    (net (code "167") (name "unconnected-(COMMUNICATION-Pad5)") (class "Default")
      (node (ref "COMMUNICATION") (pin "5") (pinfunction "5_5") (pintype "passive"))
    )
    (net (code "168") (name "unconnected-(COMMUNICATION-Pad6)") (class "Default")
      (node (ref "COMMUNICATION") (pin "6") (pinfunction "6_6") (pintype "passive"))
    )
    (net (code "169") (name "unconnected-(COMMUNICATION-Pad7)") (class "Default")
      (node (ref "COMMUNICATION") (pin "7") (pinfunction "7_7") (pintype "passive"))
    )
    (net (code "170") (name "unconnected-(COMMUNICATION-Pad8)") (class "Default")
      (node (ref "COMMUNICATION") (pin "8") (pinfunction "8_8") (pintype "passive"))
    )
    (net (code "171") (name "unconnected-(IC3-(A8)PC0-Pad53)") (class "Default")
      (node (ref "IC3") (pin "53") (pinfunction "(A8)PC0_53") (pintype "passive"))
    )
    (net (code "172") (name "unconnected-(IC3-(A9)PC1-Pad54)") (class "Default")
      (node (ref "IC3") (pin "54") (pinfunction "(A9)PC1_54") (pintype "passive"))
    )
    (net (code "173") (name "unconnected-(IC3-(A10)PC2-Pad55)") (class "Default")
      (node (ref "IC3") (pin "55") (pinfunction "(A10)PC2_55") (pintype "passive"))
    )
    (net (code "174") (name "unconnected-(IC3-(A11)PC3-Pad56)") (class "Default")
      (node (ref "IC3") (pin "56") (pinfunction "(A11)PC3_56") (pintype "passive"))
    )
    (net (code "175") (name "unconnected-(IC3-(A12)PC4-Pad57)") (class "Default")
      (node (ref "IC3") (pin "57") (pinfunction "(A12)PC4_57") (pintype "passive"))
    )
    (net (code "176") (name "unconnected-(IC3-(A13)PC5-Pad58)") (class "Default")
      (node (ref "IC3") (pin "58") (pinfunction "(A13)PC5_58") (pintype "passive"))
    )
    (net (code "177") (name "unconnected-(IC3-(A14)PC6-Pad59)") (class "Default")
      (node (ref "IC3") (pin "59") (pinfunction "(A14)PC6_59") (pintype "passive"))
    )
    (net (code "178") (name "unconnected-(IC3-(A15)PC7-Pad60)") (class "Default")
      (node (ref "IC3") (pin "60") (pinfunction "(A15)PC7_60") (pintype "passive"))
    )
    (net (code "179") (name "unconnected-(IC3-(AD0)PA0-Pad78)") (class "Default")
      (node (ref "IC3") (pin "78") (pinfunction "(AD0)PA0_78") (pintype "passive"))
    )
    (net (code "180") (name "unconnected-(IC3-(AD1)PA1-Pad77)") (class "Default")
      (node (ref "IC3") (pin "77") (pinfunction "(AD1)PA1_77") (pintype "passive"))
    )
    (net (code "181") (name "unconnected-(IC3-(AD2)PA2-Pad76)") (class "Default")
      (node (ref "IC3") (pin "76") (pinfunction "(AD2)PA2_76") (pintype "passive"))
    )
    (net (code "182") (name "unconnected-(IC3-(AD3)PA3-Pad75)") (class "Default")
      (node (ref "IC3") (pin "75") (pinfunction "(AD3)PA3_75") (pintype "passive"))
    )
    (net (code "183") (name "unconnected-(IC3-(AD4)PA4-Pad74)") (class "Default")
      (node (ref "IC3") (pin "74") (pinfunction "(AD4)PA4_74") (pintype "passive"))
    )
    (net (code "184") (name "unconnected-(IC3-(AD5)PA5-Pad73)") (class "Default")
      (node (ref "IC3") (pin "73") (pinfunction "(AD5)PA5_73") (pintype "passive"))
    )
    (net (code "185") (name "unconnected-(IC3-(AD6)PA6-Pad72)") (class "Default")
      (node (ref "IC3") (pin "72") (pinfunction "(AD6)PA6_72") (pintype "passive"))
    )
    (net (code "186") (name "unconnected-(IC3-(AD7)PA7-Pad71)") (class "Default")
      (node (ref "IC3") (pin "71") (pinfunction "(AD7)PA7_71") (pintype "passive"))
    )
    (net (code "187") (name "unconnected-(IC3-(ALE)PG2-Pad70)") (class "Default")
      (node (ref "IC3") (pin "70") (pinfunction "(ALE)PG2_70") (pintype "passive"))
    )
    (net (code "188") (name "unconnected-(IC3-(CLKO{slash}ICP3{slash}INT7)PE7-Pad9)") (class "Default")
      (node (ref "IC3") (pin "9") (pinfunction "(CLKO/ICP3/INT7)PE7_9") (pintype "passive"))
    )
    (net (code "189") (name "unconnected-(IC3-(ICP1)PD4-Pad47)") (class "Default")
      (node (ref "IC3") (pin "47") (pinfunction "(ICP1)PD4_47") (pintype "passive"))
    )
    (net (code "190") (name "unconnected-(IC3-(MISO{slash}PCINT3)PB3-Pad22)") (class "Default")
      (node (ref "IC3") (pin "22") (pinfunction "(MISO/PCINT3)PB3_22") (pintype "passive"))
    )
    (net (code "191") (name "unconnected-(IC3-(MOSI{slash}PCINT2)PB2-Pad21)") (class "Default")
      (node (ref "IC3") (pin "21") (pinfunction "(MOSI/PCINT2)PB2_21") (pintype "passive"))
    )
    (net (code "192") (name "unconnected-(IC3-(RD)PG1-Pad52)") (class "Default")
      (node (ref "IC3") (pin "52") (pinfunction "(RD)PG1_52") (pintype "passive"))
    )
    (net (code "193") (name "unconnected-(IC3-(SCK{slash}PCINT1)PB1-Pad20)") (class "Default")
      (node (ref "IC3") (pin "20") (pinfunction "(SCK/PCINT1)PB1_20") (pintype "passive"))
    )
    (net (code "194") (name "unconnected-(IC3-(SS{slash}PCINT0)PB0-Pad19)") (class "Default")
      (node (ref "IC3") (pin "19") (pinfunction "(SS/PCINT0)PB0_19") (pintype "passive"))
    )
    (net (code "195") (name "unconnected-(IC3-(T0)PD7-Pad50)") (class "Default")
      (node (ref "IC3") (pin "50") (pinfunction "(T0)PD7_50") (pintype "passive"))
    )
    (net (code "196") (name "unconnected-(IC3-(T1)PD6-Pad49)") (class "Default")
      (node (ref "IC3") (pin "49") (pinfunction "(T1)PD6_49") (pintype "passive"))
    )
    (net (code "197") (name "unconnected-(IC3-(T3{slash}INT6)PE6-Pad8)") (class "Default")
      (node (ref "IC3") (pin "8") (pinfunction "(T3/INT6)PE6_8") (pintype "passive"))
    )
    (net (code "198") (name "unconnected-(IC3-(TOSC1)PG4-Pad29)") (class "Default")
      (node (ref "IC3") (pin "29") (pinfunction "(TOSC1)PG4_29") (pintype "passive"))
    )
    (net (code "199") (name "unconnected-(IC3-(TOSC2)PG3-Pad28)") (class "Default")
      (node (ref "IC3") (pin "28") (pinfunction "(TOSC2)PG3_28") (pintype "passive"))
    )
    (net (code "200") (name "unconnected-(IC3-(WR)PG0-Pad51)") (class "Default")
      (node (ref "IC3") (pin "51") (pinfunction "(WR)PG0_51") (pintype "passive"))
    )
    (net (code "201") (name "unconnected-(IC3-(XCK0{slash}AIN0)PE2-Pad4)") (class "Default")
      (node (ref "IC3") (pin "4") (pinfunction "(XCK0/AIN0)PE2_4") (pintype "passive"))
    )
    (net (code "202") (name "unconnected-(IC3-(XCK1)PD5-Pad48)") (class "Default")
      (node (ref "IC3") (pin "48") (pinfunction "(XCK1)PD5_48") (pintype "passive"))
    )
    (net (code "203") (name "unconnected-(IC3-PH0(RXD2)-Pad12)") (class "Default")
      (node (ref "IC3") (pin "12") (pinfunction "PH0(RXD2)_12") (pintype "passive"))
    )
    (net (code "204") (name "unconnected-(IC3-PH1(TXD2)-Pad13)") (class "Default")
      (node (ref "IC3") (pin "13") (pinfunction "PH1(TXD2)_13") (pintype "passive"))
    )
    (net (code "205") (name "unconnected-(IC3-PH2(XCK2)-Pad14)") (class "Default")
      (node (ref "IC3") (pin "14") (pinfunction "PH2(XCK2)_14") (pintype "passive"))
    )
    (net (code "206") (name "unconnected-(IC3-PH3(OC4A)-Pad15)") (class "Default")
      (node (ref "IC3") (pin "15") (pinfunction "PH3(OC4A)_15") (pintype "passive"))
    )
    (net (code "207") (name "unconnected-(IC3-PH4(OC4B)-Pad16)") (class "Default")
      (node (ref "IC3") (pin "16") (pinfunction "PH4(OC4B)_16") (pintype "passive"))
    )
    (net (code "208") (name "unconnected-(IC3-PH5(OC4C)-Pad17)") (class "Default")
      (node (ref "IC3") (pin "17") (pinfunction "PH5(OC4C)_17") (pintype "passive"))
    )
    (net (code "209") (name "unconnected-(IC3-PH6(OC2B)-Pad18)") (class "Default")
      (node (ref "IC3") (pin "18") (pinfunction "PH6(OC2B)_18") (pintype "passive"))
    )
    (net (code "210") (name "unconnected-(IC3-PH7(T4)-Pad27)") (class "Default")
      (node (ref "IC3") (pin "27") (pinfunction "PH7(T4)_27") (pintype "passive"))
    )
    (net (code "211") (name "unconnected-(IC3-PJ0(RXD3{slash}PCINT9)-Pad63)") (class "Default")
      (node (ref "IC3") (pin "63") (pinfunction "PJ0(RXD3/PCINT9)_63") (pintype "passive"))
    )
    (net (code "212") (name "unconnected-(IC3-PJ1(TXD3{slash}PCINT10)-Pad64)") (class "Default")
      (node (ref "IC3") (pin "64") (pinfunction "PJ1(TXD3/PCINT10)_64") (pintype "passive"))
    )
    (net (code "213") (name "unconnected-(IC3-PJ2(XCK3{slash}PCINT11)-Pad65)") (class "Default")
      (node (ref "IC3") (pin "65") (pinfunction "PJ2(XCK3/PCINT11)_65") (pintype "passive"))
    )
    (net (code "214") (name "unconnected-(IC3-PJ3(PCINT12)-Pad66)") (class "Default")
      (node (ref "IC3") (pin "66") (pinfunction "PJ3(PCINT12)_66") (pintype "passive"))
    )
    (net (code "215") (name "unconnected-(IC3-PJ4(PCINT13)-Pad67)") (class "Default")
      (node (ref "IC3") (pin "67") (pinfunction "PJ4(PCINT13)_67") (pintype "passive"))
    )
    (net (code "216") (name "unconnected-(IC3-PJ5(PCINT14)-Pad68)") (class "Default")
      (node (ref "IC3") (pin "68") (pinfunction "PJ5(PCINT14)_68") (pintype "passive"))
    )
    (net (code "217") (name "unconnected-(IC3-PJ6(PCINT15)-Pad69)") (class "Default")
      (node (ref "IC3") (pin "69") (pinfunction "PJ6(PCINT15)_69") (pintype "passive"))
    )
    (net (code "218") (name "unconnected-(IC3-PJ7-Pad79)") (class "Default")
      (node (ref "IC3") (pin "79") (pinfunction "PJ7_79") (pintype "passive"))
    )
    (net (code "219") (name "unconnected-(IC3-PL0(ICP4)-Pad35)") (class "Default")
      (node (ref "IC3") (pin "35") (pinfunction "PL0(ICP4)_35") (pintype "passive"))
    )
    (net (code "220") (name "unconnected-(IC3-PL1(ICP5)-Pad36)") (class "Default")
      (node (ref "IC3") (pin "36") (pinfunction "PL1(ICP5)_36") (pintype "passive"))
    )
    (net (code "221") (name "unconnected-(IC3-PL2(T5)-Pad37)") (class "Default")
      (node (ref "IC3") (pin "37") (pinfunction "PL2(T5)_37") (pintype "passive"))
    )
    (net (code "222") (name "unconnected-(IC3-PL3(OC5A)-Pad38)") (class "Default")
      (node (ref "IC3") (pin "38") (pinfunction "PL3(OC5A)_38") (pintype "passive"))
    )
    (net (code "223") (name "unconnected-(IC3-PL4(OC5B)-Pad39)") (class "Default")
      (node (ref "IC3") (pin "39") (pinfunction "PL4(OC5B)_39") (pintype "passive"))
    )
    (net (code "224") (name "unconnected-(IC3-PL5(OC5C)-Pad40)") (class "Default")
      (node (ref "IC3") (pin "40") (pinfunction "PL5(OC5C)_40") (pintype "passive"))
    )
    (net (code "225") (name "unconnected-(IC3-PL6-Pad41)") (class "Default")
      (node (ref "IC3") (pin "41") (pinfunction "PL6_41") (pintype "passive"))
    )
    (net (code "226") (name "unconnected-(IC3-PL7-Pad42)") (class "Default")
      (node (ref "IC3") (pin "42") (pinfunction "PL7_42") (pintype "passive"))
    )
    (net (code "227") (name "unconnected-(IC3-RESET-Pad30)") (class "Default")
      (node (ref "IC3") (pin "30") (pinfunction "RESET_30") (pintype "passive"))
    )
    (net (code "228") (name "unconnected-(IC4-(AIN0{slash}INT1)PD1-Pad7)") (class "Default")
      (node (ref "IC4") (pin "7") (pinfunction "(AIN0/INT1)PD1_7") (pintype "passive"))
    )
    (net (code "229") (name "unconnected-(IC4-(AIN2{slash}PCINT11)PC2-Pad5)") (class "Default")
      (node (ref "IC4") (pin "5") (pinfunction "(AIN2/PCINT11)PC2_5") (pintype "passive"))
    )
    (net (code "230") (name "unconnected-(IC4-(INT4{slash}ICP1{slash}CLK0)PC7-Pad22)") (class "Default")
      (node (ref "IC4") (pin "22") (pinfunction "(INT4/ICP1/CLK0)PC7_22") (pintype "passive"))
    )
    (net (code "231") (name "unconnected-(IC4-(OC0B{slash}INT0)PD0-Pad6)") (class "Default")
      (node (ref "IC4") (pin "6") (pinfunction "(OC0B/INT0)PD0_6") (pintype "passive"))
    )
    (net (code "232") (name "unconnected-(IC4-(OC1A{slash}PCINT8)PC6-Pad23)") (class "Default")
      (node (ref "IC4") (pin "23") (pinfunction "(OC1A/PCINT8)PC6_23") (pintype "passive"))
    )
    (net (code "233") (name "unconnected-(IC4-(PCINT9{slash}OC1B)PC5-Pad25)") (class "Default")
      (node (ref "IC4") (pin "25") (pinfunction "(PCINT9/OC1B)PC5_25") (pintype "passive"))
    )
    (net (code "234") (name "unconnected-(IC4-(PCINT10)PC4-Pad26)") (class "Default")
      (node (ref "IC4") (pin "26") (pinfunction "(PCINT10)PC4_26") (pintype "passive"))
    )
    (net (code "235") (name "unconnected-(IC4-(RTS{slash}AIN5{slash}INT6)PD6-Pad12)") (class "Default")
      (node (ref "IC4") (pin "12") (pinfunction "(RTS/AIN5/INT6)PD6_12") (pintype "passive"))
    )
    (net (code "236") (name "unconnected-(IC4-(SS{slash}PCINT0)PB0-Pad14)") (class "Default")
      (node (ref "IC4") (pin "14") (pinfunction "(SS/PCINT0)PB0_14") (pintype "passive"))
    )
    (net (code "237") (name "unconnected-(IC6-NC{slash}FB-Pad4)") (class "Default")
      (node (ref "IC6") (pin "4") (pinfunction "NC/FB_4") (pintype "passive"))
    )
    (net (code "238") (name "unconnected-(POWER-Pad1)") (class "Default")
      (node (ref "POWER") (pin "1") (pinfunction "1_1") (pintype "passive"))
    )
    (net (code "239") (name "unconnected-(POWER-Pad8)") (class "Default")
      (node (ref "POWER") (pin "8") (pinfunction "8_8") (pintype "passive"))
    )
    (net (code "240") (name "unconnected-(PWML-Pad7)") (class "Default")
      (node (ref "PWML") (pin "7") (pinfunction "7_7") (pintype "passive"))
    )
    (net (code "241") (name "unconnected-(PWML-Pad8)") (class "Default")
      (node (ref "PWML") (pin "8") (pinfunction "8_8") (pintype "passive"))
    )
    (net (code "242") (name "unconnected-(RESET-5-GND-Pad5)") (class "Default")
      (node (ref "RESET") (pin "5") (pinfunction "5-GND_5") (pintype "passive"))
    )
    (net (code "243") (name "unconnected-(RN1-Pad1)") (class "Default")
      (node (ref "RN1") (pin "1") (pinfunction "1_1") (pintype "passive"))
    )
    (net (code "244") (name "unconnected-(RN1A-2-Pad8)") (class "Default")
      (node (ref "RN1") (pin "8") (pinfunction "2_8") (pintype "passive"))
    )
    (net (code "245") (name "unconnected-(RN1B-1-Pad2)") (class "Default")
      (node (ref "RN1") (pin "2") (pinfunction "1_2") (pintype "passive"))
    )
    (net (code "246") (name "unconnected-(RN1C-1-Pad3)") (class "Default")
      (node (ref "RN1") (pin "3") (pinfunction "1_3") (pintype "passive"))
    )
    (net (code "247") (name "unconnected-(RN1D-1-Pad4)") (class "Default")
      (node (ref "RN1") (pin "4") (pinfunction "1_4") (pintype "passive"))
    )
    (net (code "248") (name "unconnected-(RN1D-2-Pad5)") (class "Default")
      (node (ref "RN1") (pin "5") (pinfunction "2_5") (pintype "passive"))
    )
    (net (code "249") (name "unconnected-(RN2B-1-Pad2)") (class "Default")
      (node (ref "RN2") (pin "2") (pinfunction "1_2") (pintype "passive"))
    )
    (net (code "250") (name "unconnected-(RN2B-2-Pad7)") (class "Default")
      (node (ref "RN2") (pin "7") (pinfunction "2_7") (pintype "passive"))
    )
    (net (code "251") (name "unconnected-(RN2C-1-Pad3)") (class "Default")
      (node (ref "RN2") (pin "3") (pinfunction "1_3") (pintype "passive"))
    )
    (net (code "252") (name "unconnected-(RN2C-2-Pad6)") (class "Default")
      (node (ref "RN2") (pin "6") (pinfunction "2_6") (pintype "passive"))
    )
    (net (code "253") (name "unconnected-(RN3C-1-Pad3)") (class "Default")
      (node (ref "RN3") (pin "3") (pinfunction "1_3") (pintype "passive"))
    )
    (net (code "254") (name "unconnected-(RN3C-2-Pad6)") (class "Default")
      (node (ref "RN3") (pin "6") (pinfunction "2_6") (pintype "passive"))
    )
    (net (code "255") (name "unconnected-(RN5C-2-Pad6)") (class "Default")
      (node (ref "RN5") (pin "6") (pinfunction "2_6") (pintype "passive"))
    )
  )
)
